# AMS1117_5-3_3V.net
KiCad netlist of a schematic drawn in Altium Designer
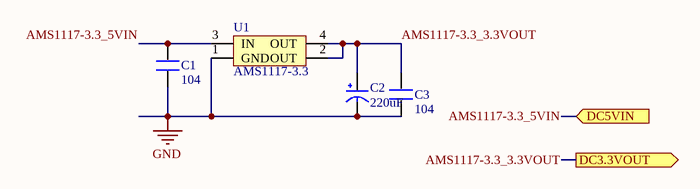
[diagram p0: AMS1117_5-3.3V.SchDoc]

(export (version "E")
  (design (tool "Eeschema 10.0.6"))
  (components
    (comp (ref "C1") (value "104") (footprint "0603P") (libsource (lib "阿波罗STM32F4&F7底板封装库") (part "C")))
    (comp (ref "C2")
      (value "220uF")
      (footprint "CC6.56.5")
      (libsource (lib "阿波罗STM32F4&F7底板封装库") (part "CAP"))
    )
    (comp (ref "C3") (value "104") (footprint "0603P") (libsource (lib "阿波罗STM32F4&F7底板封装库") (part "C")))
    (comp (ref "U1")
      (value "AMS1117-3.3")
      (footprint "AMS1117")
      (libsource (lib "阿波罗STM32F4&F7底板封装库") (part "AMS1117"))
    )
  )
  (nets
    (net (code "1") (name "/AMS1117-3.3_3.3VOUT") (class "Default")
      (node (ref "C2") (pin "1") (pinfunction "VCC_1") (pintype "passive"))
      (node (ref "C3") (pin "2") (pintype "passive"))
      (node (ref "U1") (pin "2") (pinfunction "OUT_2") (pintype "passive"))
      (node (ref "U1") (pin "4") (pinfunction "OUT_4") (pintype "passive"))
    )
    (net (code "2") (name "/AMS1117-3.3_5VIN") (class "Default")
      (node (ref "C1") (pin "2") (pintype "passive"))
      (node (ref "U1") (pin "3") (pinfunction "IN_3") (pintype "passive"))
    )
    (net (code "3") (name "GND") (class "Default")
      (node (ref "C1") (pin "1") (pintype "passive"))
      (node (ref "C2") (pin "2") (pinfunction "GND_2") (pintype "passive"))
      (node (ref "C3") (pin "1") (pintype "passive"))
      (node (ref "U1") (pin "1") (pinfunction "GND_1") (pintype "passive"))
    )
  )
)
